# Feather.net
KiCad netlist of a schematic drawn in EAGLE
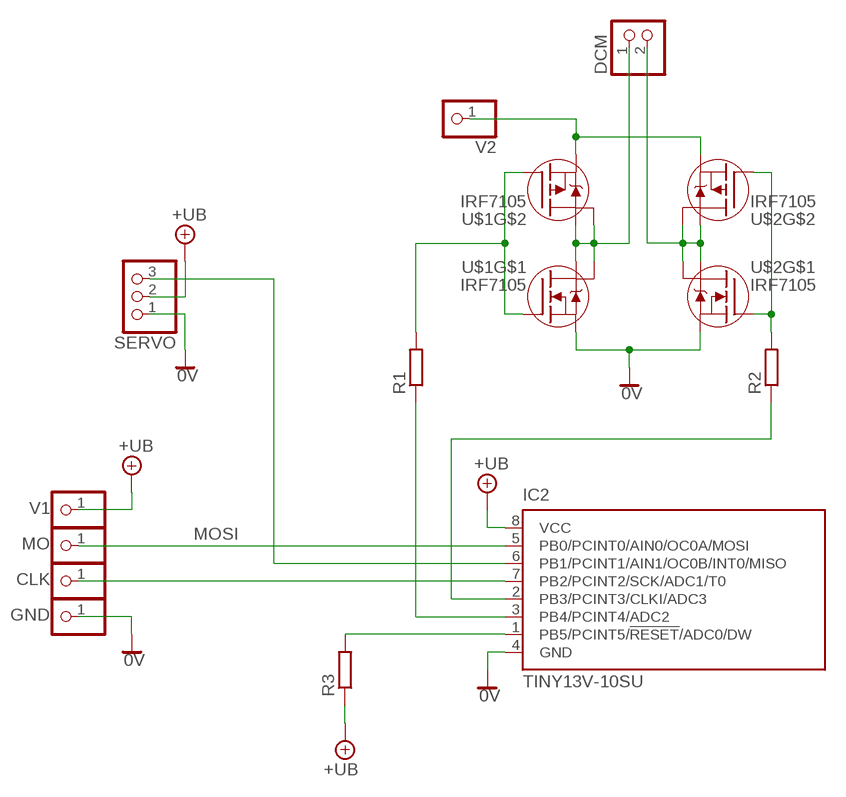
[diagram p0: schematic, sheet 1]

(export (version "E")
  (design (tool "Eeschema 10.0.6"))
  (components
    (comp (ref "CLK")
      (value "PINHD-1X1")
      (footprint "eagle-import:1X01")
      (libsource (lib "eagle-import") (part "PINHD-1X1"))
    )
    (comp (ref "DCM")
      (value "PINHD-1X2")
      (footprint "eagle-import:1X02")
      (libsource (lib "eagle-import") (part "PINHD-1X2"))
    )
    (comp (ref "GND")
      (value "PINHD-1X1")
      (footprint "eagle-import:1X01")
      (libsource (lib "eagle-import") (part "PINHD-1X1"))
    )
    (comp (ref "IC2")
      (value "TINY13V-10SU")
      (footprint "eagle-import:8S2")
      (fields (field (name "MPN") "ATTINY13V-10SU"))
      (libsource (lib "eagle-import") (part "TINY13SUV-10"))
    )
    (comp (ref "MO")
      (value "PINHD-1X1")
      (footprint "eagle-import:1X01")
      (libsource (lib "eagle-import") (part "PINHD-1X1"))
    )
    (comp (ref "R1")
      (value "R-EU_R1206")
      (footprint "eagle-import:R1206")
      (libsource (lib "eagle-import") (part "R-EU_R1206"))
    )
    (comp (ref "R2")
      (value "R-EU_R1206")
      (footprint "eagle-import:R1206")
      (libsource (lib "eagle-import") (part "R-EU_R1206"))
    )
    (comp (ref "R3")
      (value "R-EU_R1206")
      (footprint "eagle-import:R1206")
      (libsource (lib "eagle-import") (part "R-EU_R1206"))
    )
    (comp (ref "SERVO")
      (value "PINHD-1X3")
      (footprint "eagle-import:1X03")
      (libsource (lib "eagle-import") (part "PINHD-1X3"))
    )
    (comp (ref "U$1")
      (value "IRF7105")
      (footprint "eagle-import:SO8-2")
      (libsource (lib "eagle-import") (part "IRF7105"))
    )
    (comp (ref "U$2")
      (value "IRF7105")
      (footprint "eagle-import:SO8-2")
      (libsource (lib "eagle-import") (part "IRF7105"))
    )
    (comp (ref "V1")
      (value "PINHD-1X1")
      (footprint "eagle-import:1X01")
      (libsource (lib "eagle-import") (part "PINHD-1X1"))
    )
    (comp (ref "V2")
      (value "PINHD-1X1")
      (footprint "eagle-import:1X01")
      (libsource (lib "eagle-import") (part "PINHD-1X1"))
    )
  )
  (nets
    (net (code "1") (name "+UB") (class "Default")
      (node (ref "IC2") (pin "8") (pinfunction "VCC_8") (pintype "power_in"))
      (node (ref "R3") (pin "1") (pinfunction "1_1") (pintype "passive"))
      (node (ref "SERVO") (pin "2") (pinfunction "2_2") (pintype "passive"))
      (node (ref "V1") (pin "1") (pinfunction "1_1") (pintype "passive"))
    )
    (net (code "2") (name "/MOSI") (class "Default")
      (node (ref "IC2") (pin "5") (pinfunction "PB0/PCINT0/AIN0/OC0A/MOSI_5") (pintype "bidirectional"))
      (node (ref "MO") (pin "1") (pinfunction "1_1") (pintype "passive"))
    )
    (net (code "3") (name "0V") (class "Default")
      (node (ref "GND") (pin "1") (pinfunction "1_1") (pintype "passive"))
      (node (ref "IC2") (pin "4") (pinfunction "GND_4") (pintype "power_in"))
      (node (ref "SERVO") (pin "1") (pinfunction "1_1") (pintype "passive"))
      (node (ref "U$1") (pin "1") (pinfunction "S_1") (pintype "bidirectional"))
      (node (ref "U$2") (pin "1") (pinfunction "S_1") (pintype "bidirectional"))
    )
    (net (code "4") (name "Net-(DCM-Pad1)") (class "Default")
      (node (ref "DCM") (pin "1") (pinfunction "1_1") (pintype "passive"))
      (node (ref "U$1") (pin "5") (pinfunction "D_5") (pintype "bidirectional"))
      (node (ref "U$1") (pin "6") (pinfunction "D_6") (pintype "bidirectional"))
      (node (ref "U$1") (pin "7") (pinfunction "D_7") (pintype "bidirectional"))
      (node (ref "U$1") (pin "8") (pinfunction "D_8") (pintype "bidirectional"))
    )
    (net (code "5") (name "Net-(DCM-Pad2)") (class "Default")
      (node (ref "DCM") (pin "2") (pinfunction "2_2") (pintype "passive"))
      (node (ref "U$2") (pin "5") (pinfunction "D_5") (pintype "bidirectional"))
      (node (ref "U$2") (pin "6") (pinfunction "D_6") (pintype "bidirectional"))
      (node (ref "U$2") (pin "7") (pinfunction "D_7") (pintype "bidirectional"))
      (node (ref "U$2") (pin "8") (pinfunction "D_8") (pintype "bidirectional"))
    )
    (net (code "6") (name "Net-(IC2-PB1{slash}PCINT1{slash}AIN1{slash}OC0B{slash}INT0{slash}MISO)") (class "Default")
      (node (ref "IC2") (pin "6") (pinfunction "PB1/PCINT1/AIN1/OC0B/INT0/MISO_6") (pintype "bidirectional"))
      (node (ref "SERVO") (pin "3") (pinfunction "3_3") (pintype "passive"))
    )
    (net (code "7") (name "Net-(IC2-PB2{slash}PCINT2{slash}SCK{slash}ADC1{slash}T0)") (class "Default")
      (node (ref "CLK") (pin "1") (pinfunction "1_1") (pintype "passive"))
      (node (ref "IC2") (pin "7") (pinfunction "PB2/PCINT2/SCK/ADC1/T0_7") (pintype "bidirectional"))
    )
    (net (code "8") (name "Net-(IC2-PB3{slash}PCINT3{slash}CLKI{slash}ADC3)") (class "Default")
      (node (ref "IC2") (pin "2") (pinfunction "PB3/PCINT3/CLKI/ADC3_2") (pintype "bidirectional"))
      (node (ref "R2") (pin "1") (pinfunction "1_1") (pintype "passive"))
    )
    (net (code "9") (name "Net-(IC2-PB4{slash}PCINT4{slash}ADC2)") (class "Default")
      (node (ref "IC2") (pin "3") (pinfunction "PB4/PCINT4/ADC2_3") (pintype "bidirectional"))
      (node (ref "R1") (pin "1") (pinfunction "1_1") (pintype "passive"))
    )
    (net (code "10") (name "Net-(IC2-PB5{slash}PCINT5{slash}~{RESET}{slash}ADC0{slash}DW)") (class "Default")
      (node (ref "IC2") (pin "1") (pinfunction "PB5/PCINT5/~{RESET}/ADC0/DW_1") (pintype "bidirectional"))
      (node (ref "R3") (pin "2") (pinfunction "2_2") (pintype "passive"))
    )
    (net (code "11") (name "Net-(U$1A-G)") (class "Default")
      (node (ref "R1") (pin "2") (pinfunction "2_2") (pintype "passive"))
      (node (ref "U$1") (pin "2") (pinfunction "G_2") (pintype "bidirectional"))
      (node (ref "U$1") (pin "4") (pinfunction "G_4") (pintype "bidirectional"))
    )
    (net (code "12") (name "Net-(U$1B-S)") (class "Default")
      (node (ref "U$1") (pin "3") (pinfunction "S_3") (pintype "bidirectional"))
      (node (ref "U$2") (pin "3") (pinfunction "S_3") (pintype "bidirectional"))
      (node (ref "V2") (pin "1") (pinfunction "1_1") (pintype "passive"))
    )
    (net (code "13") (name "Net-(U$2A-G)") (class "Default")
      (node (ref "R2") (pin "2") (pinfunction "2_2") (pintype "passive"))
      (node (ref "U$2") (pin "2") (pinfunction "G_2") (pintype "bidirectional"))
      (node (ref "U$2") (pin "4") (pinfunction "G_4") (pintype "bidirectional"))
    )
  )
)
